# Processor_Interface.net
KiCad netlist of a schematic drawn in Altium Designer
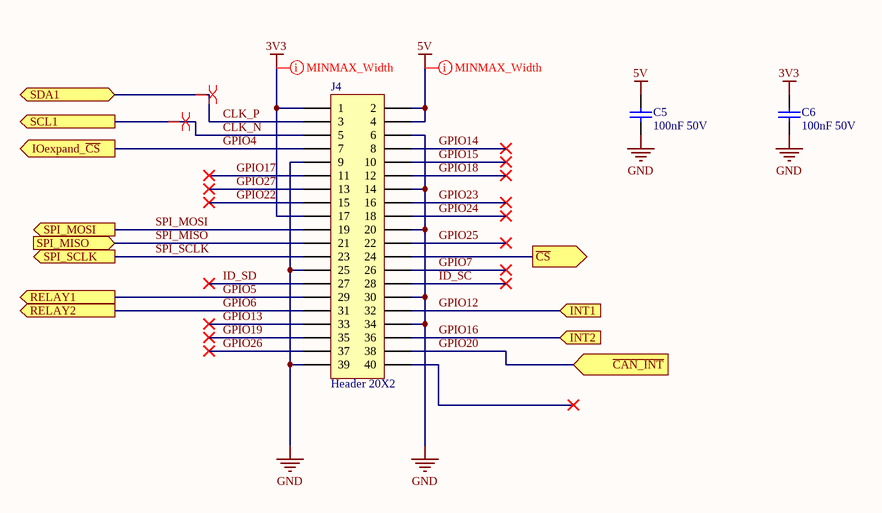
[diagram p0: Processor_Interface.SchDoc]

(export (version "E")
  (design (tool "Eeschema 10.0.6"))
  (components
    (comp (ref "C5")
      (value "100nF 50V")
      (footprint "0603C_L")
      (fields
        (field (name "MANUFACTURER") "Yageo")
        (field (name "MANUFACTURER PART NUMBER") "CC0603ZRY5V9BB104")
        (field (name "TOLERANCE") "-20%, +80%")
      )
      (libsource (lib "WCtopping") (part "Cap100nF_50V_0603"))
    )
    (comp (ref "C6")
      (value "100nF 50V")
      (footprint "0603C_L")
      (fields
        (field (name "MANUFACTURER") "Yageo")
        (field (name "MANUFACTURER PART NUMBER") "CC0603ZRY5V9BB104")
        (field (name "TOLERANCE") "-20%, +80%")
      )
      (libsource (lib "WCT") (part "Cap100nF_50V_0603"))
    )
    (comp (ref "J4")
      (value "Header 20X2")
      (footprint "HDR2X20")
      (description "Header, 20-Pin, Dual row")
      (fields (field (name "PUBLISHER") "Altium Limited"))
      (libsource (lib "Miscellaneous Connectors") (part "Header 20X2"))
    )
  )
  (nets
    (net (code "1") (name "/CLK_N") (class "Default")
      (node (ref "J4") (pin "5") (pinfunction "5_5") (pintype "passive"))
    )
    (net (code "2") (name "/CLK_P") (class "Default")
      (node (ref "J4") (pin "3") (pinfunction "3_3") (pintype "passive"))
    )
    (net (code "3") (name "/GPIO4") (class "Default")
      (node (ref "J4") (pin "7") (pinfunction "7_7") (pintype "passive"))
    )
    (net (code "4") (name "/GPIO5") (class "Default")
      (node (ref "J4") (pin "29") (pinfunction "29_29") (pintype "passive"))
    )
    (net (code "5") (name "/GPIO6") (class "Default")
      (node (ref "J4") (pin "31") (pinfunction "31_31") (pintype "passive"))
    )
    (net (code "6") (name "/GPIO7") (class "Default")
      (node (ref "J4") (pin "26") (pinfunction "26_26") (pintype "passive+no_connect"))
    )
    (net (code "7") (name "/GPIO12") (class "Default")
      (node (ref "J4") (pin "32") (pinfunction "32_32") (pintype "passive"))
    )
    (net (code "8") (name "/GPIO13") (class "Default")
      (node (ref "J4") (pin "33") (pinfunction "33_33") (pintype "passive+no_connect"))
    )
    (net (code "9") (name "/GPIO14") (class "Default")
      (node (ref "J4") (pin "8") (pinfunction "8_8") (pintype "passive+no_connect"))
    )
    (net (code "10") (name "/GPIO15") (class "Default")
      (node (ref "J4") (pin "10") (pinfunction "10_10") (pintype "passive+no_connect"))
    )
    (net (code "11") (name "/GPIO16") (class "Default")
      (node (ref "J4") (pin "36") (pinfunction "36_36") (pintype "passive"))
    )
    (net (code "12") (name "/GPIO17") (class "Default")
      (node (ref "J4") (pin "11") (pinfunction "11_11") (pintype "passive+no_connect"))
    )
    (net (code "13") (name "/GPIO18") (class "Default")
      (node (ref "J4") (pin "12") (pinfunction "12_12") (pintype "passive+no_connect"))
    )
    (net (code "14") (name "/GPIO19") (class "Default")
      (node (ref "J4") (pin "35") (pinfunction "35_35") (pintype "passive+no_connect"))
    )
    (net (code "15") (name "/GPIO20") (class "Default")
      (node (ref "J4") (pin "38") (pinfunction "38_38") (pintype "passive"))
    )
    (net (code "16") (name "/GPIO22") (class "Default")
      (node (ref "J4") (pin "15") (pinfunction "15_15") (pintype "passive+no_connect"))
    )
    (net (code "17") (name "/GPIO23") (class "Default")
      (node (ref "J4") (pin "16") (pinfunction "16_16") (pintype "passive+no_connect"))
    )
    (net (code "18") (name "/GPIO24") (class "Default")
      (node (ref "J4") (pin "18") (pinfunction "18_18") (pintype "passive+no_connect"))
    )
    (net (code "19") (name "/GPIO25") (class "Default")
      (node (ref "J4") (pin "22") (pinfunction "22_22") (pintype "passive+no_connect"))
    )
    (net (code "20") (name "/GPIO26") (class "Default")
      (node (ref "J4") (pin "37") (pinfunction "37_37") (pintype "passive+no_connect"))
    )
    (net (code "21") (name "/GPIO27") (class "Default")
      (node (ref "J4") (pin "13") (pinfunction "13_13") (pintype "passive+no_connect"))
    )
    (net (code "22") (name "/ID_SC") (class "Default")
      (node (ref "J4") (pin "28") (pinfunction "28_28") (pintype "passive+no_connect"))
    )
    (net (code "23") (name "/ID_SD") (class "Default")
      (node (ref "J4") (pin "27") (pinfunction "27_27") (pintype "passive+no_connect"))
    )
    (net (code "24") (name "/SPI_MISO") (class "Default")
      (node (ref "J4") (pin "21") (pinfunction "21_21") (pintype "passive"))
    )
    (net (code "25") (name "/SPI_MOSI") (class "Default")
      (node (ref "J4") (pin "19") (pinfunction "19_19") (pintype "passive"))
    )
    (net (code "26") (name "/SPI_SCLK") (class "Default")
      (node (ref "J4") (pin "23") (pinfunction "23_23") (pintype "passive"))
    )
    (net (code "27") (name "/~{CS}") (class "Default")
      (node (ref "J4") (pin "24") (pinfunction "24_24") (pintype "passive"))
    )
    (net (code "28") (name "3V3") (class "Default")
      (node (ref "C6") (pin "2") (pinfunction "2_2") (pintype "passive"))
      (node (ref "J4") (pin "1") (pinfunction "1_1") (pintype "passive"))
      (node (ref "J4") (pin "17") (pinfunction "17_17") (pintype "passive"))
    )
    (net (code "29") (name "5V") (class "Default")
      (node (ref "C5") (pin "2") (pinfunction "2_2") (pintype "passive"))
      (node (ref "J4") (pin "2") (pinfunction "2_2") (pintype "passive"))
      (node (ref "J4") (pin "4") (pinfunction "4_4") (pintype "passive"))
    )
    (net (code "30") (name "GND") (class "Default")
      (node (ref "C5") (pin "1") (pinfunction "1_1") (pintype "passive"))
      (node (ref "C6") (pin "1") (pinfunction "1_1") (pintype "passive"))
      (node (ref "J4") (pin "14") (pinfunction "14_14") (pintype "passive"))
      (node (ref "J4") (pin "20") (pinfunction "20_20") (pintype "passive"))
      (node (ref "J4") (pin "25") (pinfunction "25_25") (pintype "passive"))
      (node (ref "J4") (pin "30") (pinfunction "30_30") (pintype "passive"))
      (node (ref "J4") (pin "34") (pinfunction "34_34") (pintype "passive"))
      (node (ref "J4") (pin "39") (pinfunction "39_39") (pintype "passive"))
      (node (ref "J4") (pin "6") (pinfunction "6_6") (pintype "passive"))
      (node (ref "J4") (pin "9") (pinfunction "9_9") (pintype "passive"))
    )
    (net (code "31") (name "unconnected-(J4-Pad40)") (class "Default")
      (node (ref "J4") (pin "40") (pinfunction "40_40") (pintype "passive+no_connect"))
    )
  )
)
